# SWIR-LED-Board-SCH_SH2__01.net
KiCad netlist of a schematic drawn in Altium Designer
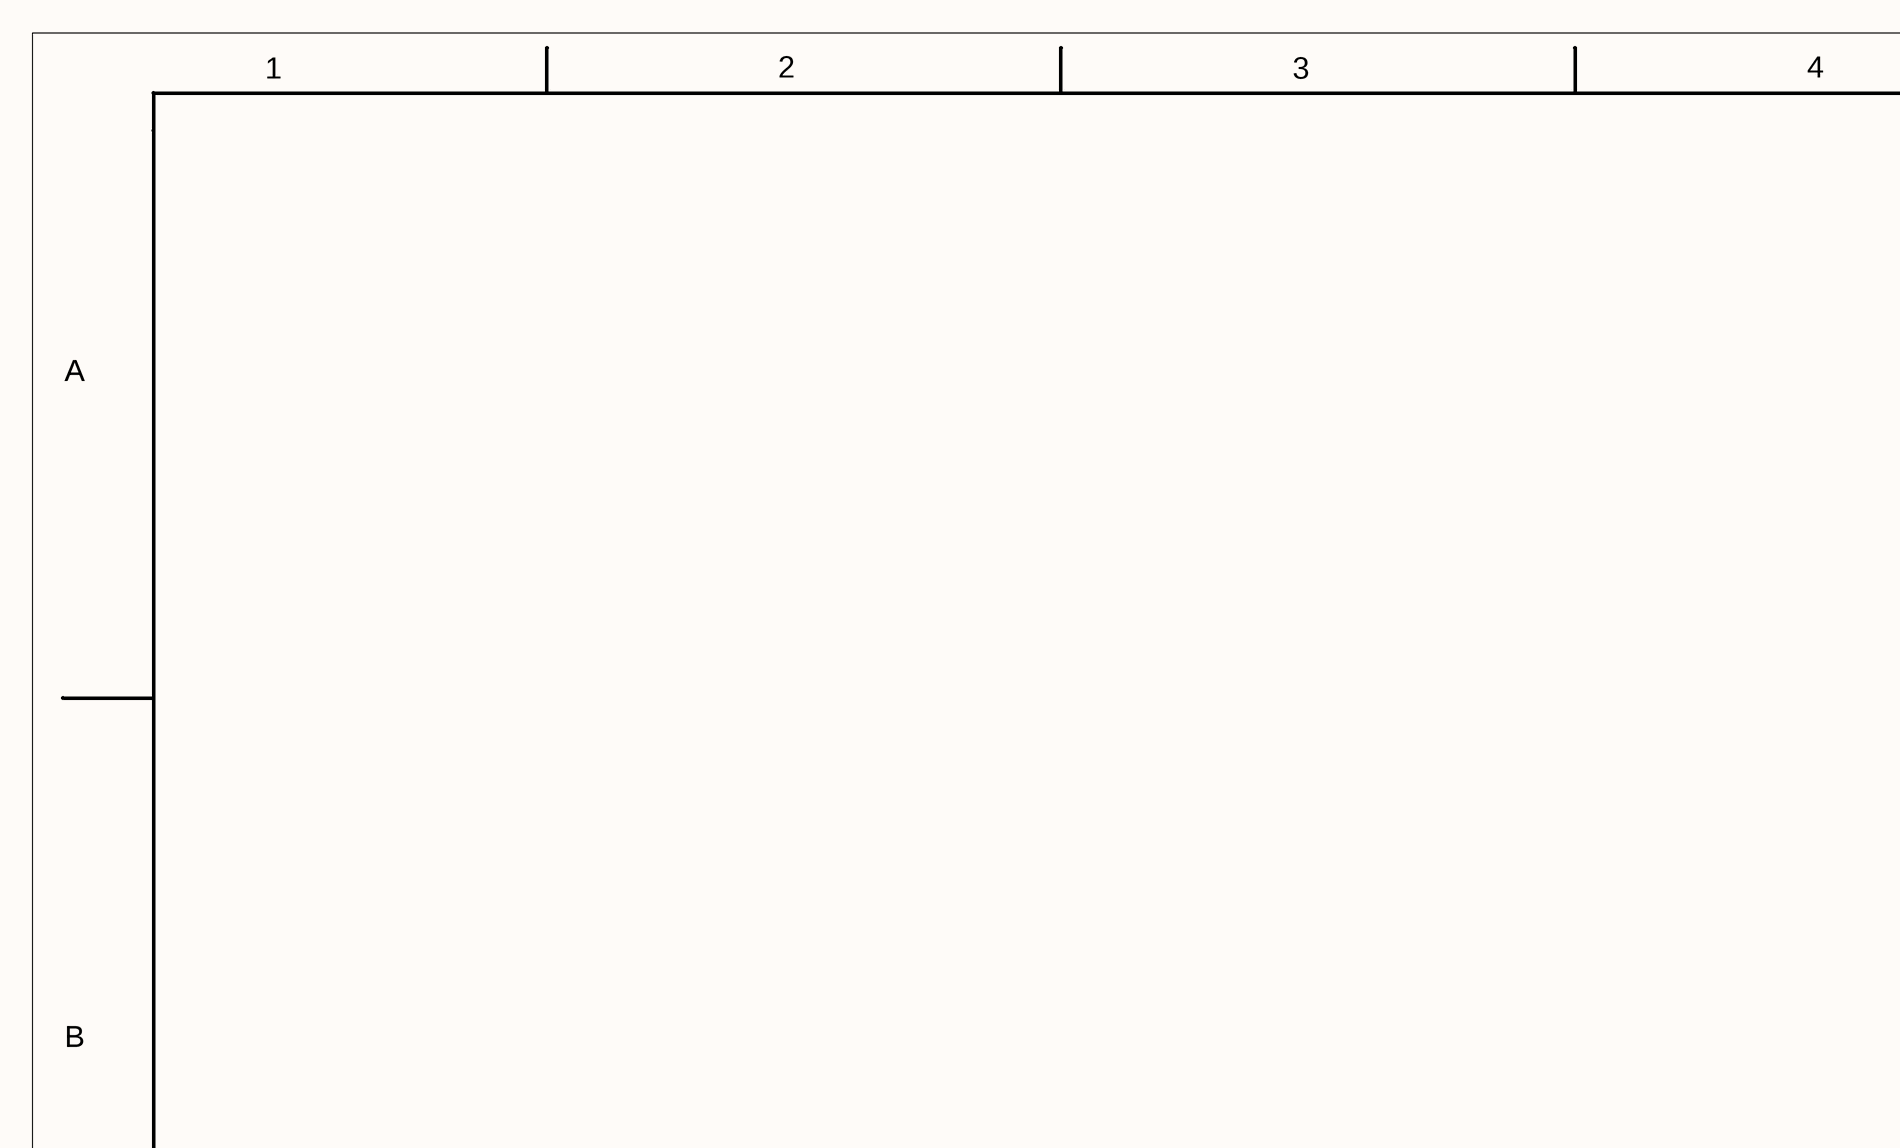
[diagram p0: SWIR-LED-Board-SCH_SH2_(01).SchDoc, top left]
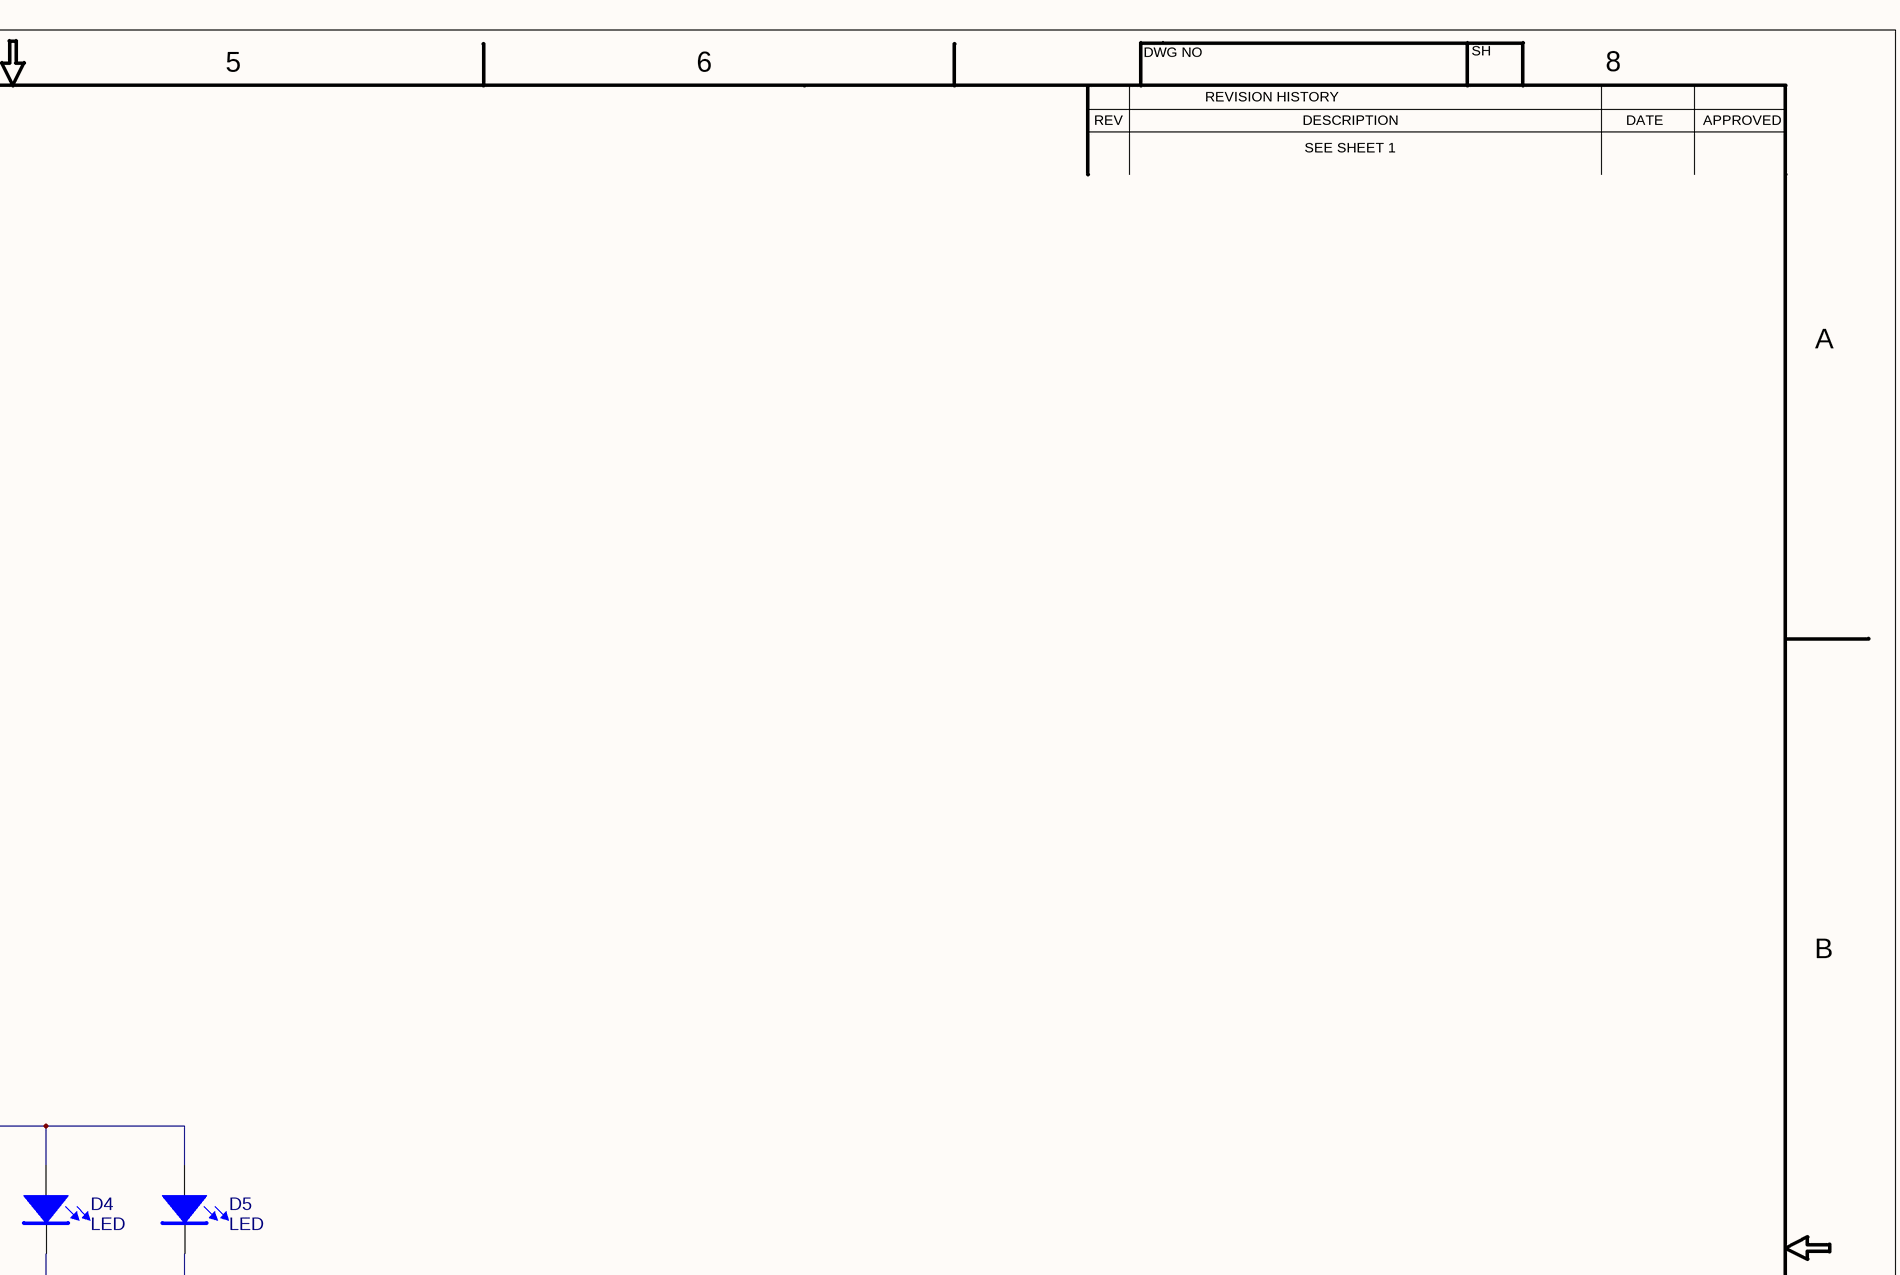
[diagram p1: SWIR-LED-Board-SCH_SH2_(01).SchDoc, top right]
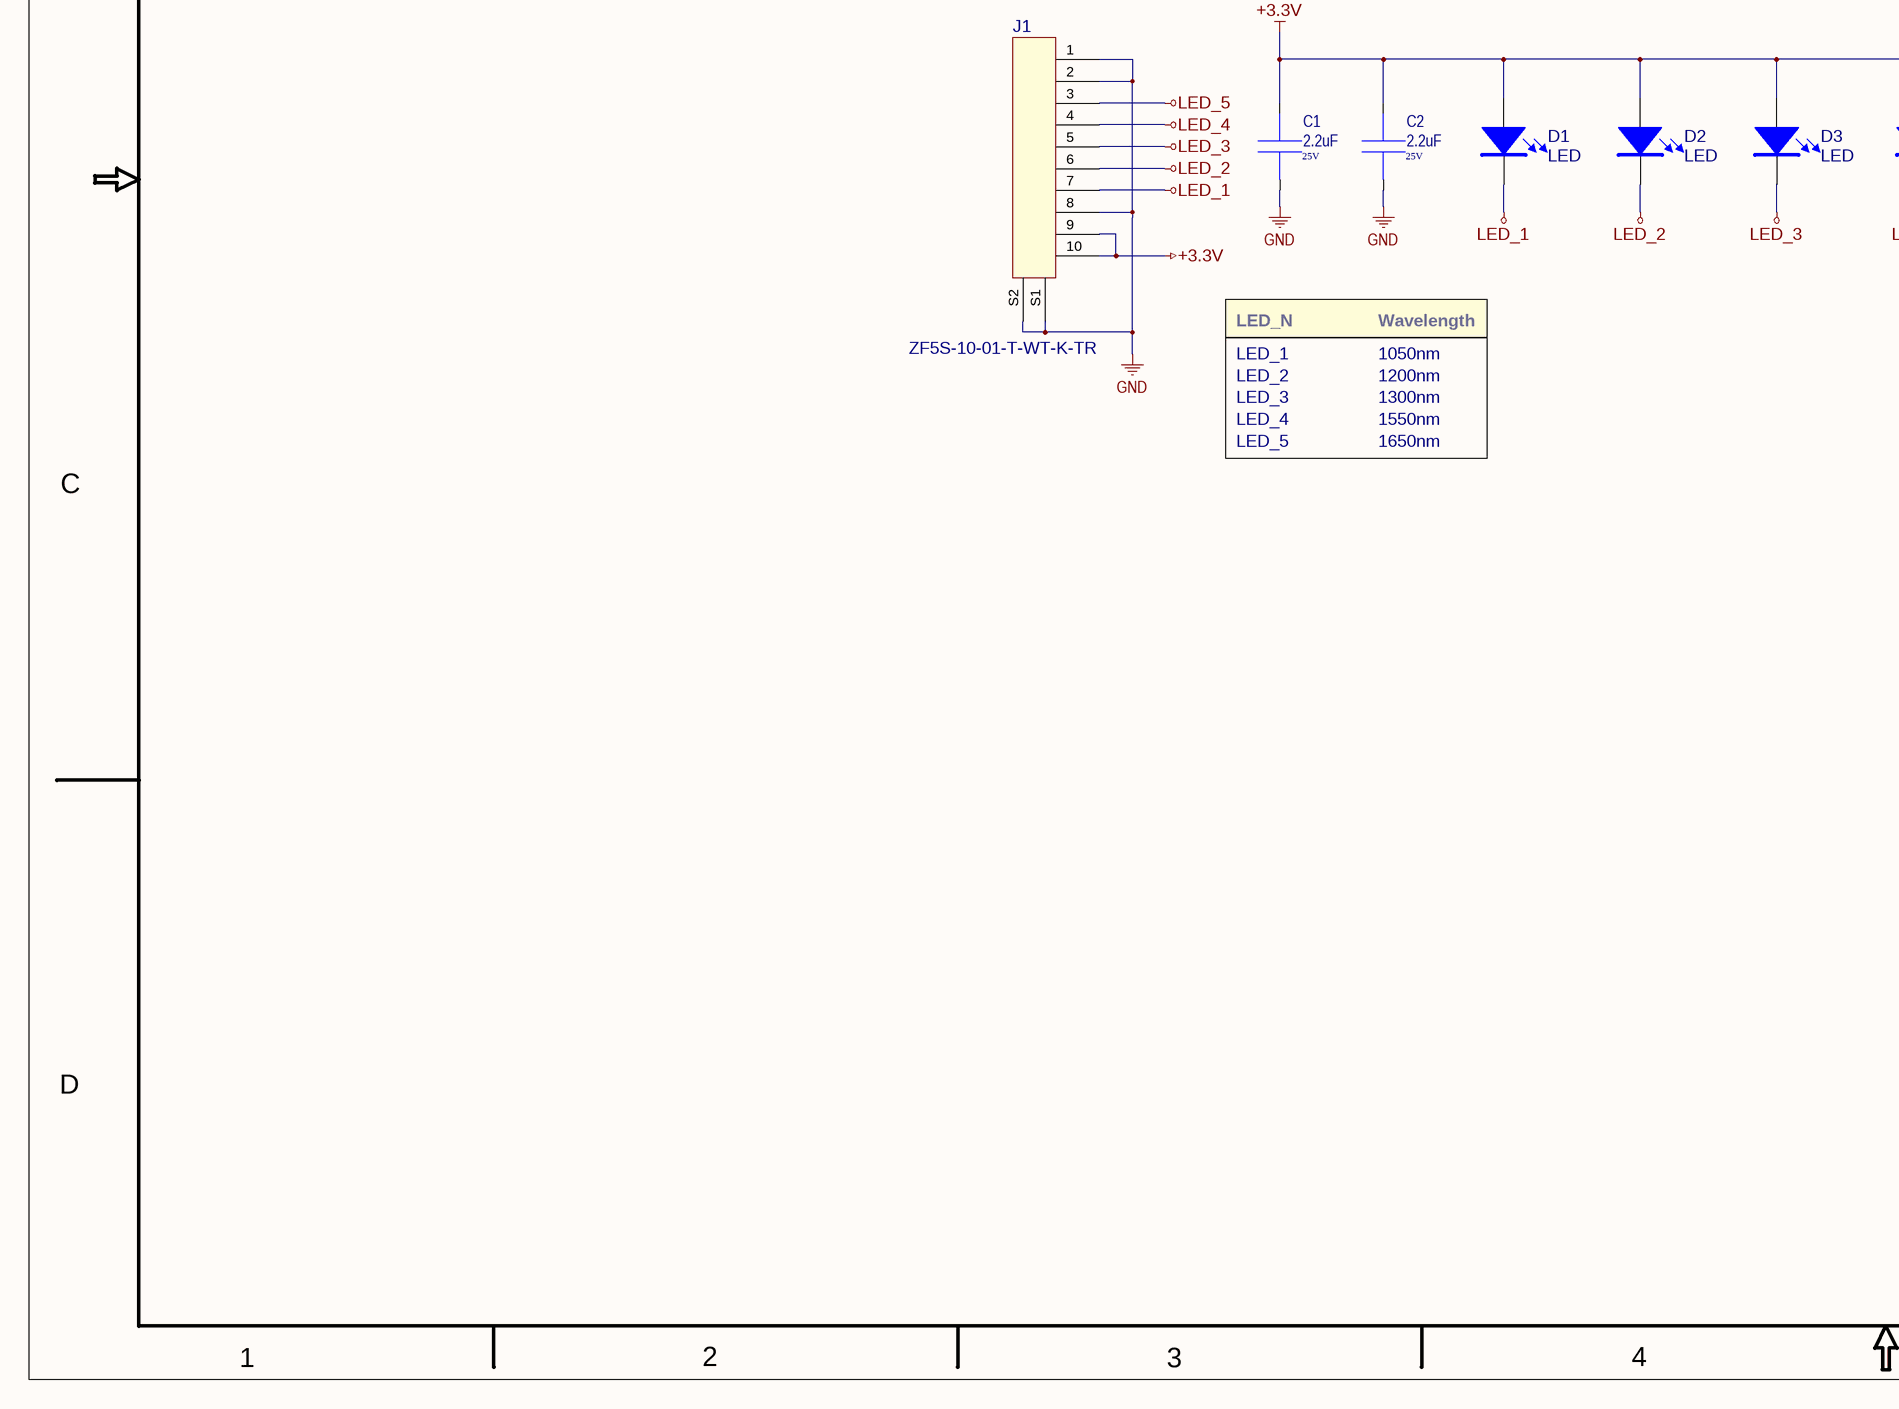
[diagram p2: SWIR-LED-Board-SCH_SH2_(01).SchDoc, bottom left]
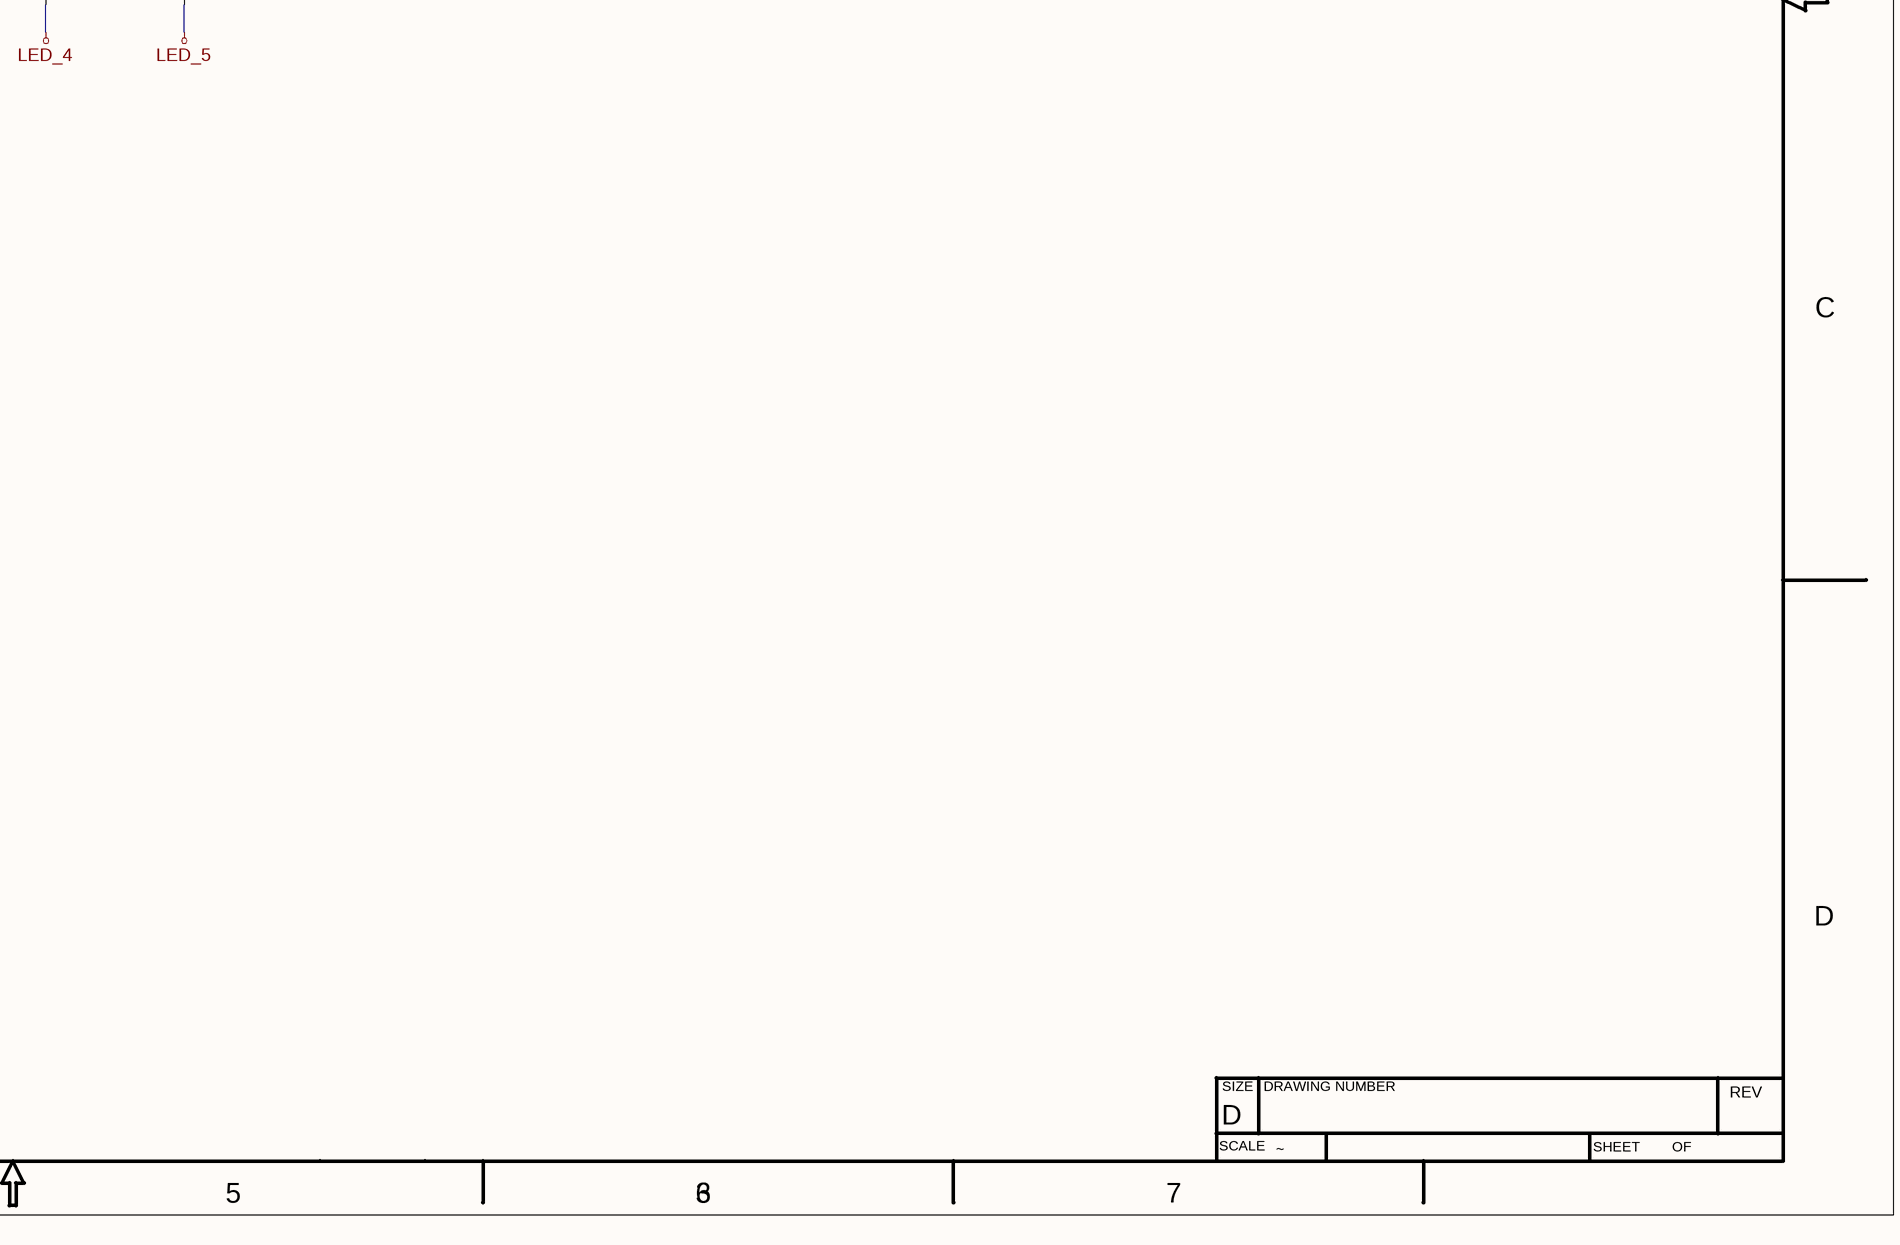
[diagram p3: SWIR-LED-Board-SCH_SH2_(01).SchDoc, bottom right]

(export (version "E")
  (design (tool "Eeschema 10.0.6"))
  (components
    (comp (ref "C1")
      (value "2.2uF")
      (footprint "0805")
      (description "CAP CER 2.2UF 25V X7R 0805")
      (fields
        (field (name "PART NUMBER") "C2012X7R1E225M085AB")
        (field (name "MANUFACTURER") "TDK")
        (field (name "VOLTAGE") "25V")
      )
      (libsource (lib "CAPACITORS") (part "CAP"))
    )
    (comp (ref "C2")
      (value "2.2uF")
      (footprint "0805")
      (description "CAP CER 2.2UF 25V X7R 0805")
      (fields
        (field (name "PART NUMBER") "C2012X7R1E225M085AB")
        (field (name "MANUFACTURER") "TDK")
        (field (name "VOLTAGE") "25V")
      )
      (libsource (lib "CAPACITORS") (part "CAP"))
    )
    (comp (ref "D1")
      (value "LED")
      (footprint "1206_LED")
      (fields (field (name "MANUFACTURER") "Marktech Optoelectronics"))
      (libsource (lib "SEMICONDUCTORS") (part "LED"))
    )
    (comp (ref "D2")
      (value "LED")
      (footprint "1206_LED")
      (fields (field (name "MANUFACTURER") "Marktech Optoelectronics"))
      (libsource (lib "SEMICONDUCTORS") (part "LED"))
    )
    (comp (ref "D3")
      (value "LED")
      (footprint "1206_LED")
      (fields (field (name "MANUFACTURER") "Marktech Optoelectronics"))
      (libsource (lib "SEMICONDUCTORS") (part "LED"))
    )
    (comp (ref "D4")
      (value "LED")
      (footprint "1206_LED")
      (fields (field (name "MANUFACTURER") "Marktech Optoelectronics"))
      (libsource (lib "SEMICONDUCTORS") (part "LED"))
    )
    (comp (ref "D5")
      (value "LED")
      (footprint "1206_LED")
      (fields (field (name "MANUFACTURER") "Marktech Optoelectronics"))
      (libsource (lib "SEMICONDUCTORS") (part "LED"))
    )
    (comp (ref "J1")
      (value "ZF5S-10-01-T-WT-K-TR")
      (footprint "ZF5S-10-01-T-WT-K-TR")
      (fields (field (name "MANUFACTURER") "Samtec"))
      (libsource (lib "ZF5S-10-01-T-WT-K-TR") (part "ZF5S-10-01-T-WT-K-TR"))
    )
  )
  (nets
    (net (code "1") (name "+3.3V") (class "Default")
      (node (ref "C1") (pin "2") (pinfunction "2_2") (pintype "passive"))
      (node (ref "C2") (pin "2") (pinfunction "2_2") (pintype "passive"))
      (node (ref "D1") (pin "1") (pinfunction "A_1") (pintype "passive"))
      (node (ref "D2") (pin "1") (pinfunction "A_1") (pintype "passive"))
      (node (ref "D3") (pin "1") (pinfunction "A_1") (pintype "passive"))
      (node (ref "D4") (pin "1") (pinfunction "A_1") (pintype "passive"))
      (node (ref "D5") (pin "1") (pinfunction "A_1") (pintype "passive"))
      (node (ref "J1") (pin "10") (pinfunction "10_10") (pintype "passive"))
      (node (ref "J1") (pin "9") (pinfunction "9_9") (pintype "passive"))
    )
    (net (code "2") (name "GND") (class "Default")
      (node (ref "C1") (pin "1") (pinfunction "1_1") (pintype "passive"))
      (node (ref "C2") (pin "1") (pinfunction "1_1") (pintype "passive"))
      (node (ref "J1") (pin "1") (pinfunction "1_1") (pintype "passive"))
      (node (ref "J1") (pin "2") (pinfunction "2_2") (pintype "passive"))
      (node (ref "J1") (pin "8") (pinfunction "8_8") (pintype "passive"))
      (node (ref "J1") (pin "S1") (pinfunction "S1_S1") (pintype "passive"))
      (node (ref "J1") (pin "S2") (pinfunction "S2_S2") (pintype "passive"))
    )
    (net (code "3") (name "LED_1") (class "Default")
      (node (ref "D1") (pin "2") (pinfunction "K_2") (pintype "passive"))
      (node (ref "J1") (pin "7") (pinfunction "7_7") (pintype "passive"))
    )
    (net (code "4") (name "LED_2") (class "Default")
      (node (ref "D2") (pin "2") (pinfunction "K_2") (pintype "passive"))
      (node (ref "J1") (pin "6") (pinfunction "6_6") (pintype "passive"))
    )
    (net (code "5") (name "LED_3") (class "Default")
      (node (ref "D3") (pin "2") (pinfunction "K_2") (pintype "passive"))
      (node (ref "J1") (pin "5") (pinfunction "5_5") (pintype "passive"))
    )
    (net (code "6") (name "LED_4") (class "Default")
      (node (ref "D4") (pin "2") (pinfunction "K_2") (pintype "passive"))
      (node (ref "J1") (pin "4") (pinfunction "4_4") (pintype "passive"))
    )
    (net (code "7") (name "LED_5") (class "Default")
      (node (ref "D5") (pin "2") (pinfunction "K_2") (pintype "passive"))
      (node (ref "J1") (pin "3") (pinfunction "3_3") (pintype "passive"))
    )
  )
)
